# design.net
KiCad netlist of a schematic drawn in Altium Designer
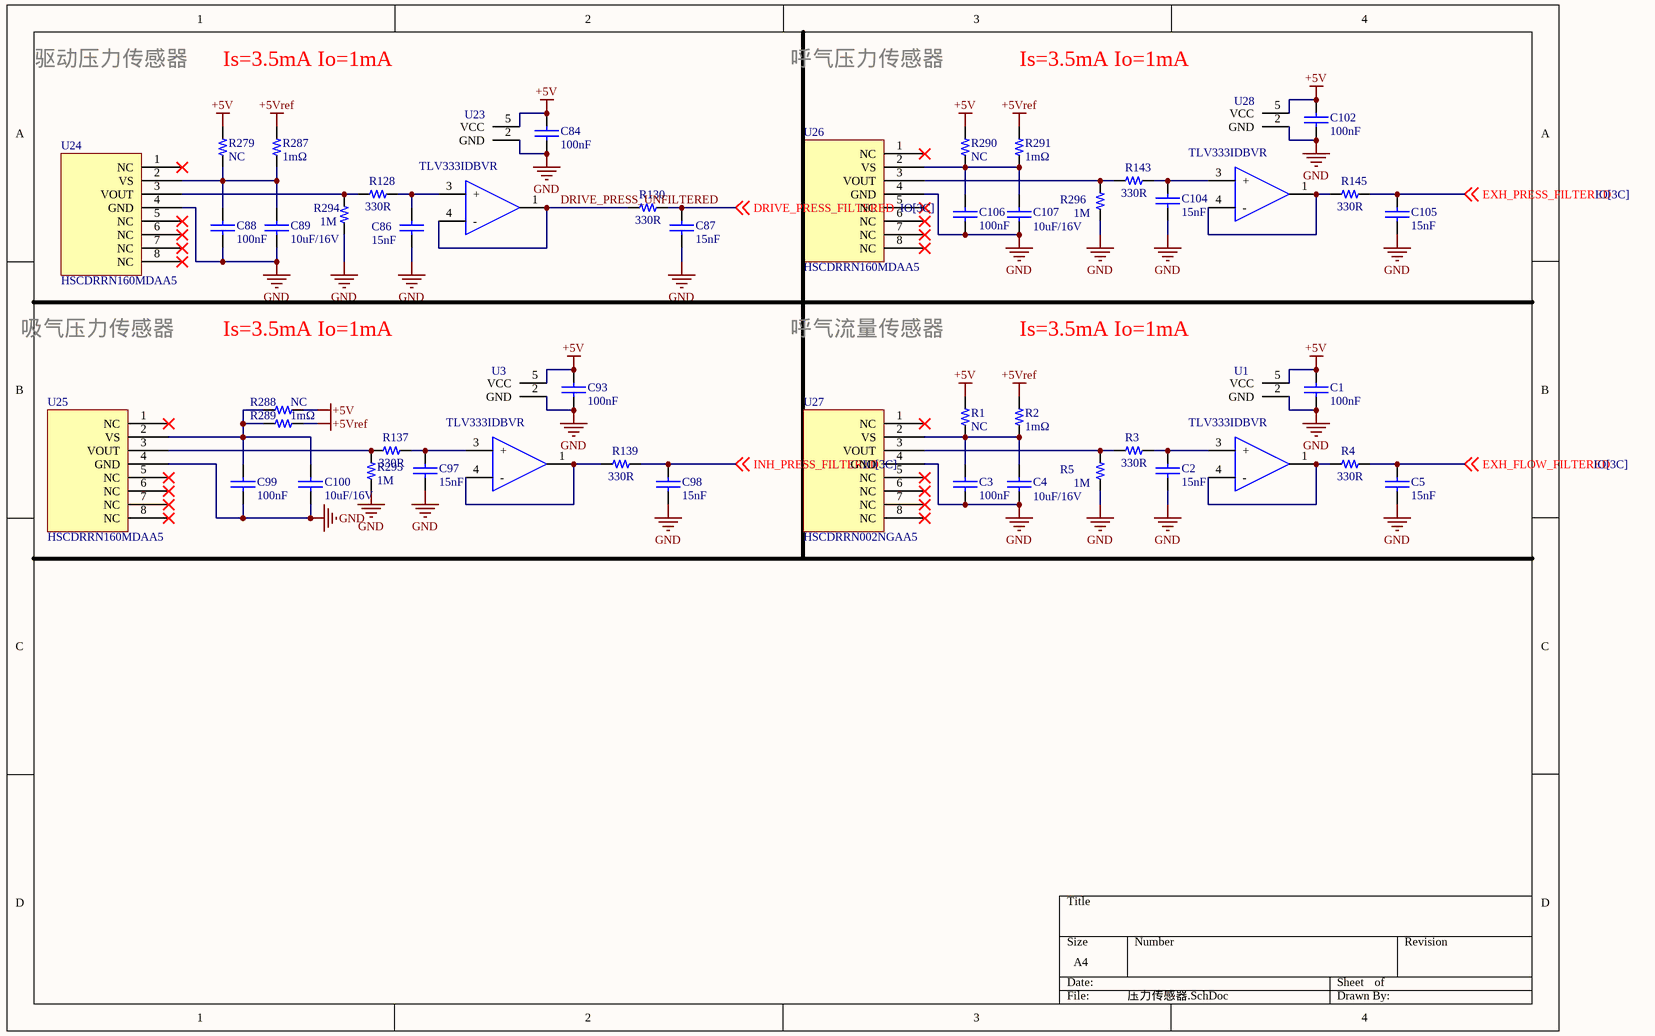
[diagram p0: 压力传感器.SchDoc]

(export (version "E")
  (design (tool "Eeschema 10.0.6"))
  (components
    (comp (ref "C1")
      (value "100nF")
      (footprint "C-0603")
      (description "Capacitor")
      (libsource (lib "*") (part "CAP"))
    )
    (comp (ref "C2")
      (value "15nF")
      (footprint "C-0603")
      (description "Capacitor")
      (libsource (lib "*") (part "CAP"))
    )
    (comp (ref "C3")
      (value "100nF")
      (footprint "C-0603")
      (description "Capacitor")
      (libsource (lib "*") (part "CAP"))
    )
    (comp (ref "C4")
      (value "10uF/16V")
      (footprint "C-0805")
      (description "Capacitor")
      (libsource (lib "*") (part "CAP"))
    )
    (comp (ref "C5")
      (value "15nF")
      (footprint "C-0603")
      (description "Capacitor")
      (libsource (lib "*") (part "CAP"))
    )
    (comp (ref "C84")
      (value "100nF")
      (footprint "C-0603")
      (description "Capacitor")
      (libsource (lib "*") (part "CAP"))
    )
    (comp (ref "C86")
      (value "15nF")
      (footprint "C-0603")
      (description "Capacitor")
      (libsource (lib "*") (part "CAP"))
    )
    (comp (ref "C87")
      (value "15nF")
      (footprint "C-0603")
      (description "Capacitor")
      (libsource (lib "*") (part "CAP"))
    )
    (comp (ref "C88")
      (value "100nF")
      (footprint "C-0603")
      (description "Capacitor")
      (libsource (lib "*") (part "CAP"))
    )
    (comp (ref "C89")
      (value "10uF/16V")
      (footprint "C-0805")
      (description "Capacitor")
      (libsource (lib "*") (part "CAP"))
    )
    (comp (ref "C93")
      (value "100nF")
      (footprint "C-0603")
      (description "Capacitor")
      (libsource (lib "*") (part "CAP"))
    )
    (comp (ref "C97")
      (value "15nF")
      (footprint "C-0603")
      (description "Capacitor")
      (libsource (lib "*") (part "CAP"))
    )
    (comp (ref "C98")
      (value "15nF")
      (footprint "C-0603")
      (description "Capacitor")
      (libsource (lib "*") (part "CAP"))
    )
    (comp (ref "C99")
      (value "100nF")
      (footprint "C-0603")
      (description "Capacitor")
      (libsource (lib "*") (part "CAP"))
    )
    (comp (ref "C100")
      (value "10uF/16V")
      (footprint "C-0805")
      (description "Capacitor")
      (libsource (lib "*") (part "CAP"))
    )
    (comp (ref "C102")
      (value "100nF")
      (footprint "C-0603")
      (description "Capacitor")
      (libsource (lib "*") (part "CAP"))
    )
    (comp (ref "C104")
      (value "15nF")
      (footprint "C-0603")
      (description "Capacitor")
      (libsource (lib "*") (part "CAP"))
    )
    (comp (ref "C105")
      (value "15nF")
      (footprint "C-0603")
      (description "Capacitor")
      (libsource (lib "*") (part "CAP"))
    )
    (comp (ref "C106")
      (value "100nF")
      (footprint "C-0603")
      (description "Capacitor")
      (libsource (lib "*") (part "CAP"))
    )
    (comp (ref "C107")
      (value "10uF/16V")
      (footprint "C-0805")
      (description "Capacitor")
      (libsource (lib "*") (part "CAP"))
    )
    (comp (ref "R1") (value "NC") (footprint "R-0603") (libsource (lib "Device") (part "R-0603")))
    (comp (ref "R2") (value "1mΩ") (footprint "R-0603") (libsource (lib "Device") (part "R-0603")))
    (comp (ref "R3") (value "330R") (footprint "R-0603") (libsource (lib "Device") (part "R-0603")))
    (comp (ref "R4") (value "330R") (footprint "R-0603") (libsource (lib "Device") (part "R-0603")))
    (comp (ref "R5") (value "1M") (footprint "R-0603") (libsource (lib "Device") (part "R-0603")))
    (comp (ref "R128") (value "330R") (footprint "R-0603") (libsource (lib "Device") (part "R-0603")))
    (comp (ref "R130") (value "330R") (footprint "R-0603") (libsource (lib "Device") (part "R-0603")))
    (comp (ref "R137") (value "330R") (footprint "R-0603") (libsource (lib "Device") (part "R-0603")))
    (comp (ref "R139") (value "330R") (footprint "R-0603") (libsource (lib "Device") (part "R-0603")))
    (comp (ref "R143") (value "330R") (footprint "R-0603") (libsource (lib "Device") (part "R-0603")))
    (comp (ref "R145") (value "330R") (footprint "R-0603") (libsource (lib "Device") (part "R-0603")))
    (comp (ref "R279") (value "NC") (footprint "R-0603") (libsource (lib "Device") (part "R-0603")))
    (comp (ref "R287") (value "1mΩ") (footprint "R-0603") (libsource (lib "Device") (part "R-0603")))
    (comp (ref "R288") (value "NC") (footprint "R-0603") (libsource (lib "Device") (part "R-0603")))
    (comp (ref "R289") (value "1mΩ") (footprint "R-0603") (libsource (lib "Device") (part "R-0603")))
    (comp (ref "R290") (value "NC") (footprint "R-0603") (libsource (lib "Device") (part "R-0603")))
    (comp (ref "R291") (value "1mΩ") (footprint "R-0603") (libsource (lib "Device") (part "R-0603")))
    (comp (ref "R294") (value "1M") (footprint "R-0603") (libsource (lib "Device") (part "R-0603")))
    (comp (ref "R295") (value "1M") (footprint "R-0603") (libsource (lib "Device") (part "R-0603")))
    (comp (ref "R296") (value "1M") (footprint "R-0603") (libsource (lib "Device") (part "R-0603")))
    (comp (ref "U1")
      (value "TLV333IDBVR")
      (footprint "SOT23-5")
      (description "品牌：TI，型号：TLV333IDBVR,SOIC-8,–25°~+85°C,单运放，ROHS")
      (libsource (lib "IC") (part "TLV333IDBVR"))
    )
    (comp (ref "U3")
      (value "TLV333IDBVR")
      (footprint "SOT23-5")
      (description "品牌：TI，型号：TLV333IDBVR,SOIC-8,–25°~+85°C,单运放，ROHS")
      (libsource (lib "IC") (part "TLV333IDBVR"))
    )
    (comp (ref "U23")
      (value "TLV333IDBVR")
      (footprint "SOT23-5")
      (description "品牌：TI，型号：TLV333IDBVR,SOIC-8,–25°~+85°C,单运放，ROHS")
      (libsource (lib "IC") (part "TLV333IDBVR"))
    )
    (comp (ref "U24")
      (value "HSCDRRN160MDAA5")
      (footprint "SSCDRR")
      (libsource (lib "NBP电源板") (part "SSCMJJ010KDAA5"))
    )
    (comp (ref "U25")
      (value "HSCDRRN160MDAA5")
      (footprint "SSCDRR")
      (libsource (lib "NBP电源板") (part "SSCMJJ010KDAA5"))
    )
    (comp (ref "U26")
      (value "HSCDRRN160MDAA5")
      (footprint "SSCDRR")
      (libsource (lib "NBP电源板") (part "SSCMJJ010KDAA5"))
    )
    (comp (ref "U27")
      (value "HSCDRRN002NGAA5")
      (footprint "SSCDRR")
      (libsource (lib "NBP电源板") (part "SSCMJJ010KDAA5"))
    )
    (comp (ref "U28")
      (value "TLV333IDBVR")
      (footprint "SOT23-5")
      (description "品牌：TI，型号：TLV333IDBVR,SOIC-8,–25°~+85°C,单运放，ROHS")
      (libsource (lib "IC") (part "TLV333IDBVR"))
    )
  )
  (nets
    (net (code "1") (name "+5V") (class "Default")
      (node (ref "C1") (pin "2") (pinfunction "2_2") (pintype "passive"))
      (node (ref "C102") (pin "2") (pinfunction "2_2") (pintype "passive"))
      (node (ref "C84") (pin "2") (pinfunction "2_2") (pintype "passive"))
      (node (ref "C93") (pin "2") (pinfunction "2_2") (pintype "passive"))
      (node (ref "R1") (pin "1") (pinfunction "1_1") (pintype "passive"))
      (node (ref "R279") (pin "1") (pinfunction "1_1") (pintype "passive"))
      (node (ref "R288") (pin "1") (pinfunction "1_1") (pintype "passive"))
      (node (ref "R290") (pin "1") (pinfunction "1_1") (pintype "passive"))
      (node (ref "U1") (pin "5") (pinfunction "VCC_5") (pintype "passive"))
      (node (ref "U23") (pin "5") (pinfunction "VCC_5") (pintype "passive"))
      (node (ref "U28") (pin "5") (pinfunction "VCC_5") (pintype "passive"))
      (node (ref "U3") (pin "5") (pinfunction "VCC_5") (pintype "passive"))
    )
    (net (code "2") (name "+5Vref") (class "Default")
      (node (ref "R2") (pin "1") (pinfunction "1_1") (pintype "passive"))
      (node (ref "R287") (pin "1") (pinfunction "1_1") (pintype "passive"))
      (node (ref "R289") (pin "1") (pinfunction "1_1") (pintype "passive"))
      (node (ref "R291") (pin "1") (pinfunction "1_1") (pintype "passive"))
    )
    (net (code "3") (name "/DRIVE_PRESS_UNFILTERED") (class "Default")
      (node (ref "R130") (pin "2") (pinfunction "2_2") (pintype "passive"))
      (node (ref "U23") (pin "1") (pintype "passive"))
      (node (ref "U23") (pin "4") (pinfunction "-_4") (pintype "passive"))
    )
    (net (code "4") (name "DRIVE_PRESS_FILTERED") (class "Default")
      (node (ref "C87") (pin "2") (pinfunction "2_2") (pintype "passive"))
      (node (ref "R130") (pin "1") (pinfunction "1_1") (pintype "passive"))
    )
    (net (code "5") (name "EXH_FLOW_FILTERED") (class "Default")
      (node (ref "C5") (pin "2") (pinfunction "2_2") (pintype "passive"))
      (node (ref "R4") (pin "1") (pinfunction "1_1") (pintype "passive"))
    )
    (net (code "6") (name "EXH_PRESS_FILTERED") (class "Default")
      (node (ref "C105") (pin "2") (pinfunction "2_2") (pintype "passive"))
      (node (ref "R145") (pin "1") (pinfunction "1_1") (pintype "passive"))
    )
    (net (code "7") (name "GND") (class "Default")
      (node (ref "C1") (pin "1") (pinfunction "1_1") (pintype "passive"))
      (node (ref "C100") (pin "1") (pinfunction "1_1") (pintype "passive"))
      (node (ref "C102") (pin "1") (pinfunction "1_1") (pintype "passive"))
      (node (ref "C104") (pin "1") (pinfunction "1_1") (pintype "passive"))
      (node (ref "C105") (pin "1") (pinfunction "1_1") (pintype "passive"))
      (node (ref "C106") (pin "1") (pinfunction "1_1") (pintype "passive"))
      (node (ref "C107") (pin "1") (pinfunction "1_1") (pintype "passive"))
      (node (ref "C2") (pin "1") (pinfunction "1_1") (pintype "passive"))
      (node (ref "C3") (pin "1") (pinfunction "1_1") (pintype "passive"))
      (node (ref "C4") (pin "1") (pinfunction "1_1") (pintype "passive"))
      (node (ref "C5") (pin "1") (pinfunction "1_1") (pintype "passive"))
      (node (ref "C84") (pin "1") (pinfunction "1_1") (pintype "passive"))
      (node (ref "C86") (pin "1") (pinfunction "1_1") (pintype "passive"))
      (node (ref "C87") (pin "1") (pinfunction "1_1") (pintype "passive"))
      (node (ref "C88") (pin "1") (pinfunction "1_1") (pintype "passive"))
      (node (ref "C89") (pin "1") (pinfunction "1_1") (pintype "passive"))
      (node (ref "C93") (pin "1") (pinfunction "1_1") (pintype "passive"))
      (node (ref "C97") (pin "1") (pinfunction "1_1") (pintype "passive"))
      (node (ref "C98") (pin "1") (pinfunction "1_1") (pintype "passive"))
      (node (ref "C99") (pin "1") (pinfunction "1_1") (pintype "passive"))
      (node (ref "R294") (pin "2") (pinfunction "2_2") (pintype "passive"))
      (node (ref "R295") (pin "2") (pinfunction "2_2") (pintype "passive"))
      (node (ref "R296") (pin "2") (pinfunction "2_2") (pintype "passive"))
      (node (ref "R5") (pin "2") (pinfunction "2_2") (pintype "passive"))
      (node (ref "U1") (pin "2") (pinfunction "GND_2") (pintype "passive"))
      (node (ref "U23") (pin "2") (pinfunction "GND_2") (pintype "passive"))
      (node (ref "U24") (pin "4") (pinfunction "GND_4") (pintype "passive"))
      (node (ref "U25") (pin "4") (pinfunction "GND_4") (pintype "passive"))
      (node (ref "U26") (pin "4") (pinfunction "GND_4") (pintype "passive"))
      (node (ref "U27") (pin "4") (pinfunction "GND_4") (pintype "passive"))
      (node (ref "U28") (pin "2") (pinfunction "GND_2") (pintype "passive"))
      (node (ref "U3") (pin "2") (pinfunction "GND_2") (pintype "passive"))
    )
    (net (code "8") (name "INH_PRESS_FILTERED") (class "Default")
      (node (ref "C98") (pin "2") (pinfunction "2_2") (pintype "passive"))
      (node (ref "R139") (pin "1") (pinfunction "1_1") (pintype "passive"))
    )
    (net (code "9") (name "Net-(U1-+)") (class "Default")
      (node (ref "C2") (pin "2") (pinfunction "2_2") (pintype "passive"))
      (node (ref "R3") (pin "1") (pinfunction "1_1") (pintype "passive"))
      (node (ref "U1") (pin "3") (pinfunction "+_3") (pintype "passive"))
    )
    (net (code "10") (name "Net-(U1--)") (class "Default")
      (node (ref "R4") (pin "2") (pinfunction "2_2") (pintype "passive"))
      (node (ref "U1") (pin "1") (pintype "passive"))
      (node (ref "U1") (pin "4") (pinfunction "-_4") (pintype "passive"))
    )
    (net (code "11") (name "Net-(U3-+)") (class "Default")
      (node (ref "C97") (pin "2") (pinfunction "2_2") (pintype "passive"))
      (node (ref "R137") (pin "1") (pinfunction "1_1") (pintype "passive"))
      (node (ref "U3") (pin "3") (pinfunction "+_3") (pintype "passive"))
    )
    (net (code "12") (name "Net-(U3--)") (class "Default")
      (node (ref "R139") (pin "2") (pinfunction "2_2") (pintype "passive"))
      (node (ref "U3") (pin "1") (pintype "passive"))
      (node (ref "U3") (pin "4") (pinfunction "-_4") (pintype "passive"))
    )
    (net (code "13") (name "Net-(U23-+)") (class "Default")
      (node (ref "C86") (pin "2") (pinfunction "2_2") (pintype "passive"))
      (node (ref "R128") (pin "1") (pinfunction "1_1") (pintype "passive"))
      (node (ref "U23") (pin "3") (pinfunction "+_3") (pintype "passive"))
    )
    (net (code "14") (name "Net-(U24-VOUT)") (class "Default")
      (node (ref "R128") (pin "2") (pinfunction "2_2") (pintype "passive"))
      (node (ref "R294") (pin "1") (pinfunction "1_1") (pintype "passive"))
      (node (ref "U24") (pin "3") (pinfunction "VOUT_3") (pintype "passive"))
    )
    (net (code "15") (name "Net-(U24-VS)") (class "Default")
      (node (ref "C88") (pin "2") (pinfunction "2_2") (pintype "passive"))
      (node (ref "C89") (pin "2") (pinfunction "2_2") (pintype "passive"))
      (node (ref "R279") (pin "2") (pinfunction "2_2") (pintype "passive"))
      (node (ref "R287") (pin "2") (pinfunction "2_2") (pintype "passive"))
      (node (ref "U24") (pin "2") (pinfunction "VS_2") (pintype "passive"))
    )
    (net (code "16") (name "Net-(U25-VOUT)") (class "Default")
      (node (ref "R137") (pin "2") (pinfunction "2_2") (pintype "passive"))
      (node (ref "R295") (pin "1") (pinfunction "1_1") (pintype "passive"))
      (node (ref "U25") (pin "3") (pinfunction "VOUT_3") (pintype "passive"))
    )
    (net (code "17") (name "Net-(U25-VS)") (class "Default")
      (node (ref "C100") (pin "2") (pinfunction "2_2") (pintype "passive"))
      (node (ref "C99") (pin "2") (pinfunction "2_2") (pintype "passive"))
      (node (ref "R288") (pin "2") (pinfunction "2_2") (pintype "passive"))
      (node (ref "R289") (pin "2") (pinfunction "2_2") (pintype "passive"))
      (node (ref "U25") (pin "2") (pinfunction "VS_2") (pintype "passive"))
    )
    (net (code "18") (name "Net-(U26-VOUT)") (class "Default")
      (node (ref "R143") (pin "2") (pinfunction "2_2") (pintype "passive"))
      (node (ref "R296") (pin "1") (pinfunction "1_1") (pintype "passive"))
      (node (ref "U26") (pin "3") (pinfunction "VOUT_3") (pintype "passive"))
    )
    (net (code "19") (name "Net-(U26-VS)") (class "Default")
      (node (ref "C106") (pin "2") (pinfunction "2_2") (pintype "passive"))
      (node (ref "C107") (pin "2") (pinfunction "2_2") (pintype "passive"))
      (node (ref "R290") (pin "2") (pinfunction "2_2") (pintype "passive"))
      (node (ref "R291") (pin "2") (pinfunction "2_2") (pintype "passive"))
      (node (ref "U26") (pin "2") (pinfunction "VS_2") (pintype "passive"))
    )
    (net (code "20") (name "Net-(U27-VOUT)") (class "Default")
      (node (ref "R3") (pin "2") (pinfunction "2_2") (pintype "passive"))
      (node (ref "R5") (pin "1") (pinfunction "1_1") (pintype "passive"))
      (node (ref "U27") (pin "3") (pinfunction "VOUT_3") (pintype "passive"))
    )
    (net (code "21") (name "Net-(U27-VS)") (class "Default")
      (node (ref "C3") (pin "2") (pinfunction "2_2") (pintype "passive"))
      (node (ref "C4") (pin "2") (pinfunction "2_2") (pintype "passive"))
      (node (ref "R1") (pin "2") (pinfunction "2_2") (pintype "passive"))
      (node (ref "R2") (pin "2") (pinfunction "2_2") (pintype "passive"))
      (node (ref "U27") (pin "2") (pinfunction "VS_2") (pintype "passive"))
    )
    (net (code "22") (name "Net-(U28-+)") (class "Default")
      (node (ref "C104") (pin "2") (pinfunction "2_2") (pintype "passive"))
      (node (ref "R143") (pin "1") (pinfunction "1_1") (pintype "passive"))
      (node (ref "U28") (pin "3") (pinfunction "+_3") (pintype "passive"))
    )
    (net (code "23") (name "Net-(U28--)") (class "Default")
      (node (ref "R145") (pin "2") (pinfunction "2_2") (pintype "passive"))
      (node (ref "U28") (pin "1") (pintype "passive"))
      (node (ref "U28") (pin "4") (pinfunction "-_4") (pintype "passive"))
    )
    (net (code "24") (name "unconnected-(U24-NC-Pad1)") (class "Default")
      (node (ref "U24") (pin "1") (pinfunction "NC_1") (pintype "passive+no_connect"))
    )
    (net (code "25") (name "unconnected-(U24-NC-Pad5)") (class "Default")
      (node (ref "U24") (pin "5") (pinfunction "NC_5") (pintype "passive+no_connect"))
    )
    (net (code "26") (name "unconnected-(U24-NC-Pad6)") (class "Default")
      (node (ref "U24") (pin "6") (pinfunction "NC_6") (pintype "passive+no_connect"))
    )
    (net (code "27") (name "unconnected-(U24-NC-Pad7)") (class "Default")
      (node (ref "U24") (pin "7") (pinfunction "NC_7") (pintype "passive+no_connect"))
    )
    (net (code "28") (name "unconnected-(U24-NC-Pad8)") (class "Default")
      (node (ref "U24") (pin "8") (pinfunction "NC_8") (pintype "passive+no_connect"))
    )
    (net (code "29") (name "unconnected-(U25-NC-Pad1)") (class "Default")
      (node (ref "U25") (pin "1") (pinfunction "NC_1") (pintype "passive+no_connect"))
    )
    (net (code "30") (name "unconnected-(U25-NC-Pad5)") (class "Default")
      (node (ref "U25") (pin "5") (pinfunction "NC_5") (pintype "passive+no_connect"))
    )
    (net (code "31") (name "unconnected-(U25-NC-Pad6)") (class "Default")
      (node (ref "U25") (pin "6") (pinfunction "NC_6") (pintype "passive+no_connect"))
    )
    (net (code "32") (name "unconnected-(U25-NC-Pad7)") (class "Default")
      (node (ref "U25") (pin "7") (pinfunction "NC_7") (pintype "passive+no_connect"))
    )
    (net (code "33") (name "unconnected-(U25-NC-Pad8)") (class "Default")
      (node (ref "U25") (pin "8") (pinfunction "NC_8") (pintype "passive+no_connect"))
    )
    (net (code "34") (name "unconnected-(U26-NC-Pad1)") (class "Default")
      (node (ref "U26") (pin "1") (pinfunction "NC_1") (pintype "passive+no_connect"))
    )
    (net (code "35") (name "unconnected-(U26-NC-Pad5)") (class "Default")
      (node (ref "U26") (pin "5") (pinfunction "NC_5") (pintype "passive+no_connect"))
    )
    (net (code "36") (name "unconnected-(U26-NC-Pad6)") (class "Default")
      (node (ref "U26") (pin "6") (pinfunction "NC_6") (pintype "passive+no_connect"))
    )
    (net (code "37") (name "unconnected-(U26-NC-Pad7)") (class "Default")
      (node (ref "U26") (pin "7") (pinfunction "NC_7") (pintype "passive+no_connect"))
    )
    (net (code "38") (name "unconnected-(U26-NC-Pad8)") (class "Default")
      (node (ref "U26") (pin "8") (pinfunction "NC_8") (pintype "passive+no_connect"))
    )
    (net (code "39") (name "unconnected-(U27-NC-Pad1)") (class "Default")
      (node (ref "U27") (pin "1") (pinfunction "NC_1") (pintype "passive+no_connect"))
    )
    (net (code "40") (name "unconnected-(U27-NC-Pad5)") (class "Default")
      (node (ref "U27") (pin "5") (pinfunction "NC_5") (pintype "passive+no_connect"))
    )
    (net (code "41") (name "unconnected-(U27-NC-Pad6)") (class "Default")
      (node (ref "U27") (pin "6") (pinfunction "NC_6") (pintype "passive+no_connect"))
    )
    (net (code "42") (name "unconnected-(U27-NC-Pad7)") (class "Default")
      (node (ref "U27") (pin "7") (pinfunction "NC_7") (pintype "passive+no_connect"))
    )
    (net (code "43") (name "unconnected-(U27-NC-Pad8)") (class "Default")
      (node (ref "U27") (pin "8") (pinfunction "NC_8") (pintype "passive+no_connect"))
    )
  )
)
